# main.net
KiCad netlist of a schematic drawn in EAGLE
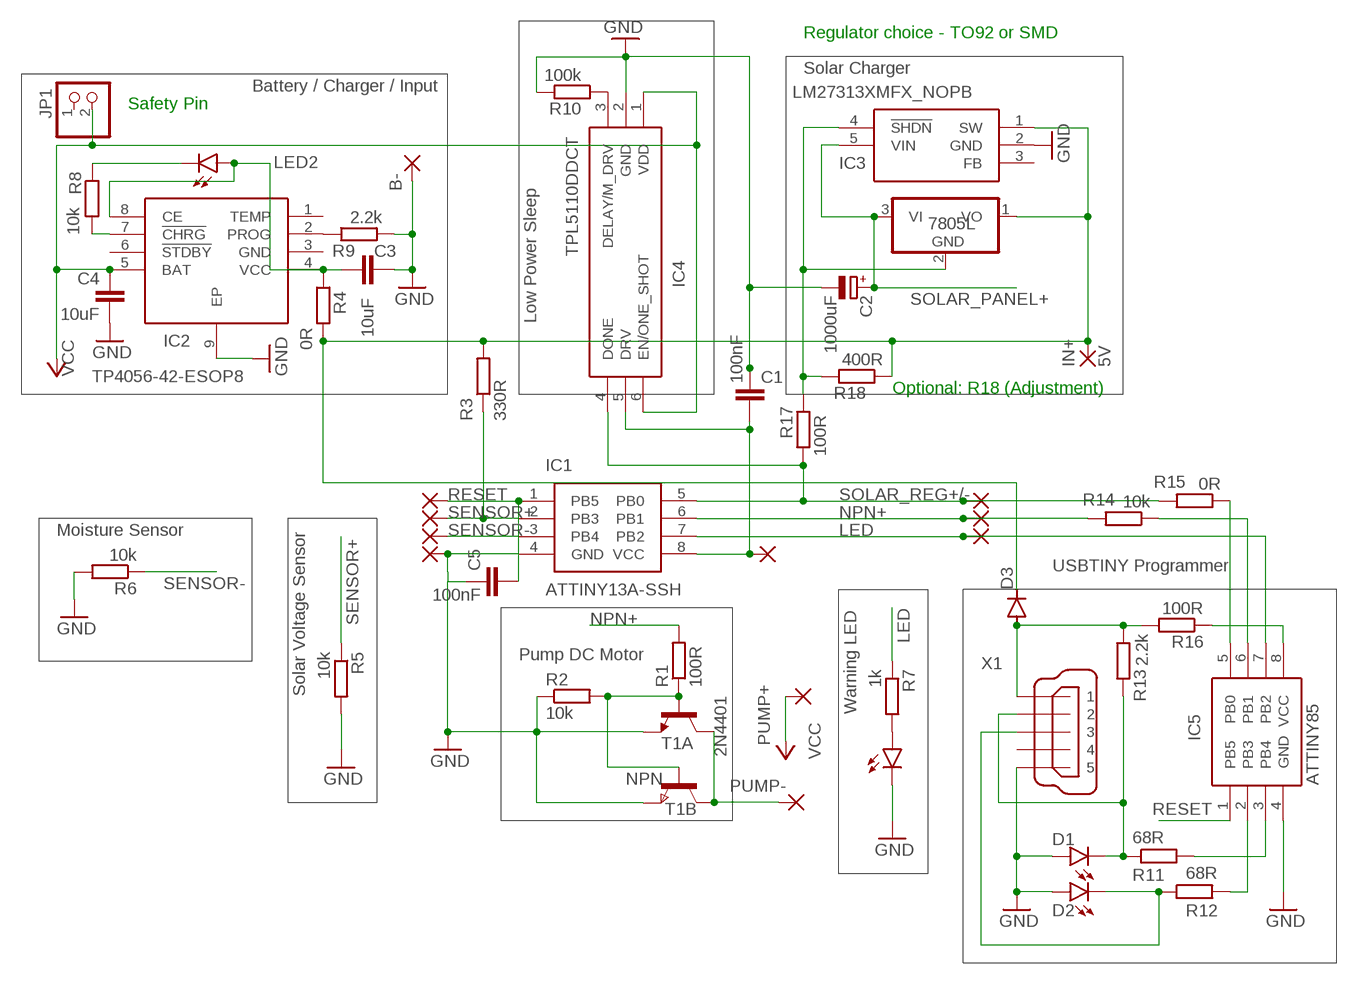
[diagram p0: schematic, sheet 1]

(export (version "E")
  (design (tool "Eeschema 10.0.6"))
  (components
    (comp (ref "B-")
      (value "1,6/0,8")
      (footprint "eagle-import:1,6_0,8")
      (libsource (lib "eagle-import") (part "1,6/0,8"))
    )
    (comp (ref "C1")
      (value "100nF")
      (footprint "eagle-import:C0805")
      (libsource (lib "eagle-import") (part "C-EUC0805"))
    )
    (comp (ref "C2")
      (value "1000uF")
      (footprint "eagle-import:E2,5-7")
      (libsource (lib "eagle-import") (part "CPOL-EUE2.5-7"))
    )
    (comp (ref "C3")
      (value "10uF")
      (footprint "eagle-import:C3216")
      (libsource (lib "eagle-import") (part "C-EUC3216"))
    )
    (comp (ref "C4")
      (value "10uF")
      (footprint "eagle-import:C0805")
      (libsource (lib "eagle-import") (part "C-EUC0805"))
    )
    (comp (ref "C5")
      (value "100nF")
      (footprint "eagle-import:C0805")
      (libsource (lib "eagle-import") (part "C-EUC0805"))
    )
    (comp (ref "D1")
      (value "LEDSML0805")
      (footprint "eagle-import:SML0805")
      (libsource (lib "eagle-import") (part "LEDSML0805"))
    )
    (comp (ref "D2")
      (value "LEDSML0805")
      (footprint "eagle-import:SML0805")
      (libsource (lib "eagle-import") (part "LEDSML0805"))
    )
    (comp (ref "D3")
      (value "DIODE-MINIMELF")
      (footprint "eagle-import:MINIMELF")
      (libsource (lib "eagle-import") (part "DIODE-MINIMELF"))
    )
    (comp (ref "IC1")
      (value "ATTINY13A-SSH")
      (footprint "eagle-import:SOIC127P600X175-8N")
      (fields
        (field (name "MOUSER_PART_NUMBER") "556-ATTINY13A-SSH")
        (field (name "RS_PART_NUMBER") "1330955")
      )
      (libsource (lib "eagle-import") (part "ATTINY13A-SSH"))
    )
    (comp (ref "IC2")
      (value "TP4056-42-ESOP8")
      (footprint "eagle-import:SOIC127P600X175-9N")
      (libsource (lib "eagle-import") (part "TP4056-42-ESOP8"))
    )
    (comp (ref "IC3")
      (value "LM27313XMFX_NOPB")
      (footprint "eagle-import:SOT95P280X145-5N")
      (fields
        (field (name "MANUFACTURER_PART_NUMBER") "LM27313XMFX/NOPB")
        (field (name "MOUSER_PART_NUMBER") "926-LM27313XMFX/NOPB")
      )
      (libsource (lib "eagle-import") (part "LM27313XMFX_NOPB"))
    )
    (comp (ref "IC4")
      (value "TPL5110DDCT")
      (footprint "eagle-import:SOT95P280X110-6N")
      (fields
        (field (name "MOUSER_PART_NUMBER") "595-TPL5110DDCT")
        (field (name "RS_PART_NUMBER") "9009867P")
      )
      (libsource (lib "eagle-import") (part "TPL5110DDCT"))
    )
    (comp (ref "IC5")
      (value "ATTINY13A-SSH")
      (footprint "eagle-import:SOIC127P600X175-8N")
      (fields
        (field (name "MOUSER_PART_NUMBER") "556-ATTINY13A-SSH")
        (field (name "RS_PART_NUMBER") "1330955")
      )
      (libsource (lib "eagle-import") (part "ATTINY13A-SSH"))
    )
    (comp (ref "IN+")
      (value "5V")
      (footprint "eagle-import:1,6_0,9")
      (libsource (lib "eagle-import") (part "1,6/0,9"))
    )
    (comp (ref "JP1")
      (value "PINHD-1X2")
      (footprint "eagle-import:1X02")
      (libsource (lib "eagle-import") (part "PINHD-1X2"))
    )
    (comp (ref "LED1")
      (value "LEDSML0805")
      (footprint "eagle-import:SML0805")
      (libsource (lib "eagle-import") (part "LEDSML0805"))
    )
    (comp (ref "LED2")
      (value "LEDSML0805")
      (footprint "eagle-import:SML0805")
      (libsource (lib "eagle-import") (part "LEDSML0805"))
    )
    (comp (ref "PAD3")
      (value "1,6/0,8")
      (footprint "eagle-import:1,6_0,8")
      (fields (field (name "SPICEPREFIX") "X"))
      (libsource (lib "eagle-import") (part "1,6/0,8"))
    )
    (comp (ref "PAD4")
      (value "1,6/0,8")
      (footprint "eagle-import:1,6_0,8")
      (libsource (lib "eagle-import") (part "1,6/0,8"))
    )
    (comp (ref "PAD5")
      (value "1,6/0,8")
      (footprint "eagle-import:1,6_0,8")
      (libsource (lib "eagle-import") (part "1,6/0,8"))
    )
    (comp (ref "PAD6")
      (value "1,6/0,8")
      (footprint "eagle-import:1,6_0,8")
      (libsource (lib "eagle-import") (part "1,6/0,8"))
    )
    (comp (ref "PAD7")
      (value "1,6/0,8")
      (footprint "eagle-import:1,6_0,8")
      (libsource (lib "eagle-import") (part "1,6/0,8"))
    )
    (comp (ref "PAD8")
      (value "1,6/0,8")
      (footprint "eagle-import:1,6_0,8")
      (libsource (lib "eagle-import") (part "1,6/0,8"))
    )
    (comp (ref "PAD9")
      (value "1,6/0,8")
      (footprint "eagle-import:1,6_0,8")
      (libsource (lib "eagle-import") (part "1,6/0,8"))
    )
    (comp (ref "PAD10")
      (value "1,6/0,8")
      (footprint "eagle-import:1,6_0,8")
      (libsource (lib "eagle-import") (part "1,6/0,8"))
    )
    (comp (ref "PUMP+")
      (value "2,15/1,0")
      (footprint "eagle-import:2,15_1,0")
      (libsource (lib "eagle-import") (part "2,15/1,0"))
    )
    (comp (ref "PUMP-")
      (value "2,15/1,0")
      (footprint "eagle-import:2,15_1,0")
      (libsource (lib "eagle-import") (part "2,15/1,0"))
    )
    (comp (ref "R1")
      (value "100R")
      (footprint "eagle-import:R0805")
      (libsource (lib "eagle-import") (part "resistor_348_R-EU_R0805"))
    )
    (comp (ref "R2")
      (value "10k")
      (footprint "eagle-import:R0805")
      (libsource (lib "eagle-import") (part "resistor_348_R-EU_R0805"))
    )
    (comp (ref "R3")
      (value "330R")
      (footprint "eagle-import:R0805")
      (libsource (lib "eagle-import") (part "resistor_348_R-EU_R0805"))
    )
    (comp (ref "R4")
      (value "0R")
      (footprint "eagle-import:M1206")
      (libsource (lib "eagle-import") (part "resistor_348_R-EU_M1206"))
    )
    (comp (ref "R5")
      (value "10k")
      (footprint "eagle-import:R0805")
      (libsource (lib "eagle-import") (part "resistor_348_R-EU_R0805"))
    )
    (comp (ref "R6")
      (value "10k")
      (footprint "eagle-import:R0805")
      (libsource (lib "eagle-import") (part "resistor_348_R-EU_R0805"))
    )
    (comp (ref "R7")
      (value "1k")
      (footprint "eagle-import:R0805")
      (libsource (lib "eagle-import") (part "resistor_348_R-EU_R0805"))
    )
    (comp (ref "R8")
      (value "10k")
      (footprint "eagle-import:R0603")
      (libsource (lib "eagle-import") (part "R-EU_R0603"))
    )
    (comp (ref "R9")
      (value "2.2k")
      (footprint "eagle-import:R0603")
      (libsource (lib "eagle-import") (part "R-EU_R0603"))
    )
    (comp (ref "R10")
      (value "100k")
      (footprint "eagle-import:R0603")
      (libsource (lib "eagle-import") (part "resistor_348_R-EU_R0603"))
    )
    (comp (ref "R11")
      (value "68R")
      (footprint "eagle-import:R0603")
      (libsource (lib "eagle-import") (part "resistor_348_R-EU_R0603"))
    )
    (comp (ref "R12")
      (value "68R")
      (footprint "eagle-import:R0603")
      (libsource (lib "eagle-import") (part "resistor_348_R-EU_R0603"))
    )
    (comp (ref "R13")
      (value "2.2k")
      (footprint "eagle-import:R0603")
      (libsource (lib "eagle-import") (part "resistor_348_R-EU_R0603"))
    )
    (comp (ref "R14")
      (value "10k")
      (footprint "eagle-import:R0402")
      (libsource (lib "eagle-import") (part "resistor_348_R-EU_R0402"))
    )
    (comp (ref "R15")
      (value "0R")
      (footprint "eagle-import:R0402")
      (libsource (lib "eagle-import") (part "resistor_348_R-EU_R0402"))
    )
    (comp (ref "R16")
      (value "100R")
      (footprint "eagle-import:R0603")
      (libsource (lib "eagle-import") (part "resistor_348_R-EU_R0603"))
    )
    (comp (ref "R17")
      (value "100R")
      (footprint "eagle-import:R0603")
      (libsource (lib "eagle-import") (part "resistor_348_R-EU_R0603"))
    )
    (comp (ref "R18")
      (value "400R")
      (footprint "eagle-import:R0603")
      (libsource (lib "eagle-import") (part "resistor_348_R-EU_R0603"))
    )
    (comp (ref "REG1")
      (value "7805L")
      (footprint "eagle-import:TO92")
      (libsource (lib "eagle-import") (part "78L05"))
    )
    (comp (ref "T1A")
      (value "2N4401")
      (footprint "eagle-import:TO92")
      (libsource (lib "eagle-import") (part "-NPN-TO92"))
    )
    (comp (ref "T1B")
      (value "NPN")
      (footprint "eagle-import:SOT-23")
      (fields (field (name "MPN") "DSS20201L-7"))
      (libsource (lib "eagle-import") (part "NPNSOT23"))
    )
    (comp (ref "X1")
      (value "MINI-USB-UX60A-MB-5ST")
      (footprint "eagle-import:UX60A-MB-5ST")
      (libsource (lib "eagle-import") (part "MINI-USB-UX60A-MB-5ST"))
    )
  )
  (nets
    (net (code "1") (name "/LED") (class "Default")
      (node (ref "IC1") (pin "7") (pinfunction "PB2_7") (pintype "bidirectional"))
      (node (ref "IC5") (pin "7") (pinfunction "PB2_7") (pintype "bidirectional"))
      (node (ref "PAD4") (pin "1") (pinfunction "P_1") (pintype "passive"))
      (node (ref "R7") (pin "1") (pinfunction "1_1") (pintype "passive"))
    )
    (net (code "2") (name "/NPN+") (class "Default")
      (node (ref "IC1") (pin "6") (pinfunction "PB1_6") (pintype "bidirectional"))
      (node (ref "PAD6") (pin "1") (pinfunction "P_1") (pintype "passive"))
      (node (ref "R1") (pin "2") (pinfunction "2_2") (pintype "passive"))
      (node (ref "R14") (pin "2") (pinfunction "2_2") (pintype "passive"))
    )
    (net (code "3") (name "/RESET") (class "Default")
      (node (ref "C5") (pin "2") (pinfunction "2_2") (pintype "passive"))
      (node (ref "IC1") (pin "1") (pinfunction "PB5_1") (pintype "bidirectional"))
      (node (ref "IC5") (pin "1") (pinfunction "PB5_1") (pintype "bidirectional"))
      (node (ref "PAD10") (pin "1") (pinfunction "P_1") (pintype "passive"))
    )
    (net (code "4") (name "/SENSOR+") (class "Default")
      (node (ref "IC1") (pin "2") (pinfunction "PB3_2") (pintype "bidirectional"))
      (node (ref "PAD9") (pin "1") (pinfunction "P_1") (pintype "passive"))
      (node (ref "R3") (pin "1") (pinfunction "1_1") (pintype "passive"))
      (node (ref "R5") (pin "1") (pinfunction "1_1") (pintype "passive"))
    )
    (net (code "5") (name "/SENSOR-") (class "Default")
      (node (ref "IC1") (pin "3") (pinfunction "PB4_3") (pintype "bidirectional"))
      (node (ref "PAD8") (pin "1") (pinfunction "P_1") (pintype "passive"))
      (node (ref "R6") (pin "1") (pinfunction "1_1") (pintype "passive"))
    )
    (net (code "6") (name "/SOLAR_PANEL+") (class "Default")
      (node (ref "C2") (pin "+") (pinfunction "+_+") (pintype "passive"))
      (node (ref "IC3") (pin "5") (pinfunction "VIN_5") (pintype "bidirectional"))
      (node (ref "REG1") (pin "3") (pinfunction "VI_3") (pintype "input"))
    )
    (net (code "7") (name "/SOLAR_REG+{slash}-") (class "Default")
      (node (ref "IC1") (pin "5") (pinfunction "PB0_5") (pintype "bidirectional"))
      (node (ref "IC4") (pin "4") (pinfunction "DONE_4") (pintype "bidirectional"))
      (node (ref "PAD5") (pin "1") (pinfunction "P_1") (pintype "passive"))
      (node (ref "R15") (pin "2") (pinfunction "2_2") (pintype "passive"))
      (node (ref "R17") (pin "1") (pinfunction "1_1") (pintype "passive"))
    )
    (net (code "8") (name "GND") (class "Default")
      (node (ref "B-") (pin "1") (pinfunction "P_1") (pintype "passive"))
      (node (ref "C1") (pin "1") (pinfunction "1_1") (pintype "passive"))
      (node (ref "C2") (pin "-") (pinfunction "-_-") (pintype "passive"))
      (node (ref "C3") (pin "2") (pinfunction "2_2") (pintype "passive"))
      (node (ref "C4") (pin "2") (pinfunction "2_2") (pintype "passive"))
      (node (ref "C5") (pin "1") (pinfunction "1_1") (pintype "passive"))
      (node (ref "D1") (pin "A") (pinfunction "A_A") (pintype "passive"))
      (node (ref "D2") (pin "A") (pinfunction "A_A") (pintype "passive"))
      (node (ref "IC1") (pin "4") (pinfunction "GND_4") (pintype "bidirectional"))
      (node (ref "IC2") (pin "9") (pinfunction "EP_9") (pintype "bidirectional"))
      (node (ref "IC3") (pin "2") (pinfunction "GND_2") (pintype "bidirectional"))
      (node (ref "IC4") (pin "2") (pinfunction "GND_2") (pintype "bidirectional"))
      (node (ref "IC5") (pin "4") (pinfunction "GND_4") (pintype "bidirectional"))
      (node (ref "LED1") (pin "C") (pinfunction "C_C") (pintype "passive"))
      (node (ref "PAD7") (pin "1") (pinfunction "P_1") (pintype "passive"))
      (node (ref "R10") (pin "2") (pinfunction "2_2") (pintype "passive"))
      (node (ref "R2") (pin "1") (pinfunction "1_1") (pintype "passive"))
      (node (ref "R5") (pin "2") (pinfunction "2_2") (pintype "passive"))
      (node (ref "R6") (pin "2") (pinfunction "2_2") (pintype "passive"))
      (node (ref "R9") (pin "2") (pinfunction "2_2") (pintype "passive"))
      (node (ref "T1A") (pin "1") (pinfunction "E_1") (pintype "passive"))
      (node (ref "T1B") (pin "2") (pinfunction "E_2") (pintype "passive"))
      (node (ref "X1") (pin "5") (pinfunction "5_5") (pintype "input"))
    )
    (net (code "9") (name "Net-(D1-PadC)") (class "Default")
      (node (ref "D1") (pin "C") (pinfunction "C_C") (pintype "passive"))
      (node (ref "R11") (pin "1") (pinfunction "1_1") (pintype "passive"))
      (node (ref "R13") (pin "2") (pinfunction "2_2") (pintype "passive"))
      (node (ref "X1") (pin "2") (pinfunction "2_2") (pintype "input"))
    )
    (net (code "10") (name "Net-(D2-PadC)") (class "Default")
      (node (ref "D2") (pin "C") (pinfunction "C_C") (pintype "passive"))
      (node (ref "R12") (pin "1") (pinfunction "1_1") (pintype "passive"))
      (node (ref "X1") (pin "3") (pinfunction "3_3") (pintype "input"))
    )
    (net (code "11") (name "Net-(D3-PadA)") (class "Default")
      (node (ref "D3") (pin "A") (pinfunction "A_A") (pintype "passive"))
      (node (ref "R13") (pin "1") (pinfunction "1_1") (pintype "passive"))
      (node (ref "R16") (pin "2") (pinfunction "2_2") (pintype "passive"))
      (node (ref "X1") (pin "1") (pinfunction "1_1") (pintype "input"))
    )
    (net (code "12") (name "Net-(IC1-VCC)") (class "Default")
      (node (ref "C1") (pin "2") (pinfunction "2_2") (pintype "passive"))
      (node (ref "IC1") (pin "8") (pinfunction "VCC_8") (pintype "bidirectional"))
      (node (ref "IC4") (pin "5") (pinfunction "DRV_5") (pintype "bidirectional"))
      (node (ref "PAD3") (pin "1") (pinfunction "P_1") (pintype "passive"))
    )
    (net (code "13") (name "Net-(IC2-CE)") (class "Default")
      (node (ref "C3") (pin "1") (pinfunction "1_1") (pintype "passive"))
      (node (ref "IC2") (pin "4") (pinfunction "VCC_4") (pintype "bidirectional"))
      (node (ref "IC2") (pin "8") (pinfunction "CE_8") (pintype "bidirectional"))
      (node (ref "LED2") (pin "A") (pinfunction "A_A") (pintype "passive"))
      (node (ref "R4") (pin "2") (pinfunction "2_2") (pintype "passive"))
    )
    (net (code "14") (name "Net-(IC2-PROG)") (class "Default")
      (node (ref "IC2") (pin "2") (pinfunction "PROG_2") (pintype "bidirectional"))
      (node (ref "R9") (pin "1") (pinfunction "1_1") (pintype "passive"))
    )
    (net (code "15") (name "Net-(IC2-~{CHRG})") (class "Default")
      (node (ref "IC2") (pin "7") (pinfunction "~{CHRG}_7") (pintype "bidirectional"))
      (node (ref "R8") (pin "2") (pinfunction "2_2") (pintype "passive"))
    )
    (net (code "16") (name "Net-(IC3-SW)") (class "Default")
      (node (ref "D3") (pin "C") (pinfunction "C_C") (pintype "passive"))
      (node (ref "IC3") (pin "1") (pinfunction "SW_1") (pintype "bidirectional"))
      (node (ref "IN+") (pin "1") (pinfunction "P_1") (pintype "passive"))
      (node (ref "R18") (pin "1") (pinfunction "1_1") (pintype "passive"))
      (node (ref "R3") (pin "2") (pinfunction "2_2") (pintype "passive"))
      (node (ref "R4") (pin "1") (pinfunction "1_1") (pintype "passive"))
      (node (ref "REG1") (pin "1") (pinfunction "VO_1") (pintype "passive"))
    )
    (net (code "17") (name "Net-(IC3-~{SHDN})") (class "Default")
      (node (ref "IC3") (pin "4") (pinfunction "~{SHDN}_4") (pintype "bidirectional"))
      (node (ref "R17") (pin "2") (pinfunction "2_2") (pintype "passive"))
      (node (ref "R18") (pin "2") (pinfunction "2_2") (pintype "passive"))
      (node (ref "REG1") (pin "2") (pinfunction "GND_2") (pintype "passive"))
    )
    (net (code "18") (name "Net-(IC4-DELAY{slash}M_DRV)") (class "Default")
      (node (ref "IC4") (pin "3") (pinfunction "DELAY/M_DRV_3") (pintype "bidirectional"))
      (node (ref "R10") (pin "1") (pinfunction "1_1") (pintype "passive"))
    )
    (net (code "19") (name "Net-(IC5-PB0)") (class "Default")
      (node (ref "IC5") (pin "5") (pinfunction "PB0_5") (pintype "bidirectional"))
      (node (ref "R15") (pin "1") (pinfunction "1_1") (pintype "passive"))
    )
    (net (code "20") (name "Net-(IC5-PB1)") (class "Default")
      (node (ref "IC5") (pin "6") (pinfunction "PB1_6") (pintype "bidirectional"))
      (node (ref "R14") (pin "1") (pinfunction "1_1") (pintype "passive"))
    )
    (net (code "21") (name "Net-(IC5-PB3)") (class "Default")
      (node (ref "IC5") (pin "2") (pinfunction "PB3_2") (pintype "bidirectional"))
      (node (ref "R12") (pin "2") (pinfunction "2_2") (pintype "passive"))
    )
    (net (code "22") (name "Net-(IC5-PB4)") (class "Default")
      (node (ref "IC5") (pin "3") (pinfunction "PB4_3") (pintype "bidirectional"))
      (node (ref "R11") (pin "2") (pinfunction "2_2") (pintype "passive"))
    )
    (net (code "23") (name "Net-(IC5-VCC)") (class "Default")
      (node (ref "IC5") (pin "8") (pinfunction "VCC_8") (pintype "bidirectional"))
      (node (ref "R16") (pin "1") (pinfunction "1_1") (pintype "passive"))
    )
    (net (code "24") (name "Net-(LED1-PadA)") (class "Default")
      (node (ref "LED1") (pin "A") (pinfunction "A_A") (pintype "passive"))
      (node (ref "R7") (pin "2") (pinfunction "2_2") (pintype "passive"))
    )
    (net (code "25") (name "Net-(LED2-PadC)") (class "Default")
      (node (ref "LED2") (pin "C") (pinfunction "C_C") (pintype "passive"))
      (node (ref "R8") (pin "1") (pinfunction "1_1") (pintype "passive"))
    )
    (net (code "26") (name "Net-(PUMP--P)") (class "Default")
      (node (ref "PUMP-") (pin "1") (pinfunction "P_1") (pintype "passive"))
      (node (ref "T1A") (pin "3") (pinfunction "C_3") (pintype "passive"))
      (node (ref "T1B") (pin "1") (pinfunction "C_1") (pintype "passive"))
    )
    (net (code "27") (name "Net-(T1A-B)") (class "Default")
      (node (ref "R1") (pin "1") (pinfunction "1_1") (pintype "passive"))
      (node (ref "R2") (pin "2") (pinfunction "2_2") (pintype "passive"))
      (node (ref "T1A") (pin "2") (pinfunction "B_2") (pintype "passive"))
      (node (ref "T1B") (pin "3") (pinfunction "B_3") (pintype "passive"))
    )
    (net (code "28") (name "VCC") (class "Default")
      (node (ref "C4") (pin "1") (pinfunction "1_1") (pintype "passive"))
      (node (ref "IC2") (pin "5") (pinfunction "BAT_5") (pintype "bidirectional"))
      (node (ref "IC4") (pin "1") (pinfunction "VDD_1") (pintype "bidirectional"))
      (node (ref "IC4") (pin "6") (pinfunction "EN/ONE_SHOT_6") (pintype "bidirectional"))
      (node (ref "JP1") (pin "2") (pinfunction "2_2") (pintype "passive"))
      (node (ref "PUMP+") (pin "1") (pinfunction "P_1") (pintype "passive"))
    )
    (net (code "29") (name "unconnected-(IC2-GND-Pad3)") (class "Default")
      (node (ref "IC2") (pin "3") (pinfunction "GND_3") (pintype "bidirectional"))
    )
    (net (code "30") (name "unconnected-(IC2-TEMP-Pad1)") (class "Default")
      (node (ref "IC2") (pin "1") (pinfunction "TEMP_1") (pintype "bidirectional"))
    )
    (net (code "31") (name "unconnected-(IC2-~{STDBY}-Pad6)") (class "Default")
      (node (ref "IC2") (pin "6") (pinfunction "~{STDBY}_6") (pintype "bidirectional"))
    )
    (net (code "32") (name "unconnected-(IC3-FB-Pad3)") (class "Default")
      (node (ref "IC3") (pin "3") (pinfunction "FB_3") (pintype "bidirectional"))
    )
    (net (code "33") (name "unconnected-(JP1-Pad1)") (class "Default")
      (node (ref "JP1") (pin "1") (pinfunction "1_1") (pintype "passive"))
    )
    (net (code "34") (name "unconnected-(X1-Pad4)") (class "Default")
      (node (ref "X1") (pin "4") (pinfunction "4_4") (pintype "input"))
    )
  )
)
